# Power-Supply.net
KiCad netlist of a schematic drawn in Altium Designer
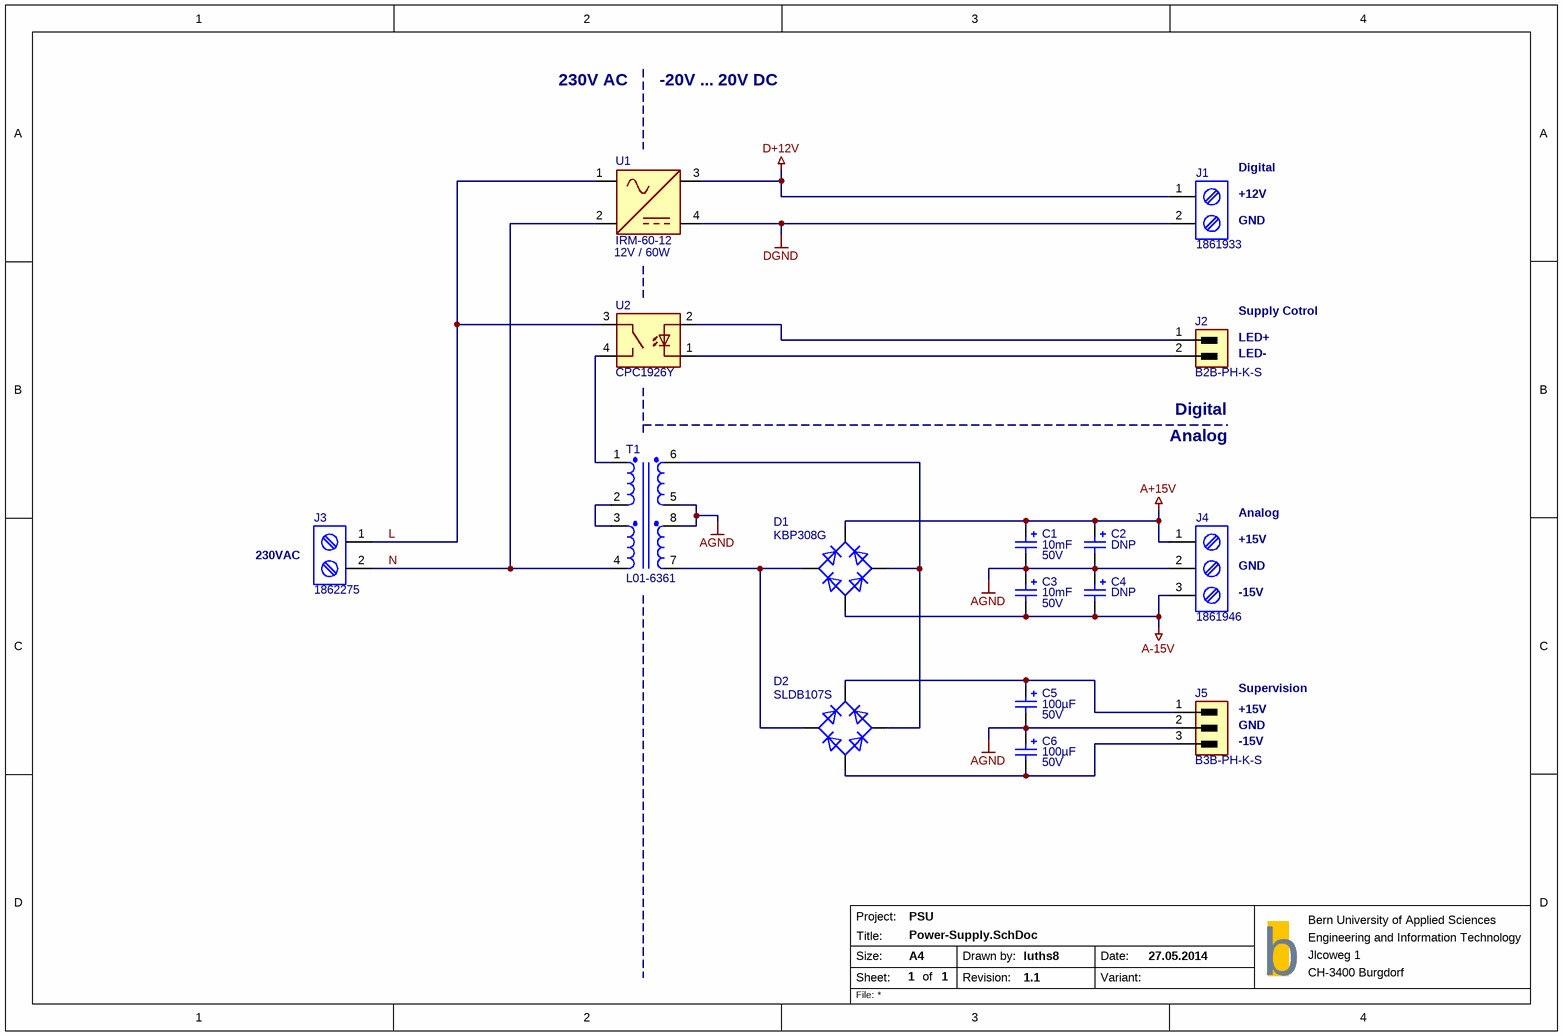
[diagram p0: Power-Supply.SchDoc]

(export (version "E")
  (design (tool "Eeschema 10.0.6"))
  (components
    (comp (ref "C1")
      (value "10mF")
      (footprint "CAP-25-50-12.5 - duplicate")
      (description "Elektrolytic Capacitor")
      (fields (field (name "VOLTAGE") "50V") (field (name "MANUFACTURER PART NO.") "UKW1H103MRD"))
      (libsource (lib "Audio-Streamer") (part "Capacitor Electrolytic"))
    )
    (comp (ref "C2")
      (value "DNP")
      (footprint "CAP-25-50-12.5 - duplicate")
      (description "Elektrolytic Capacitor")
      (fields (field (name "VOLTAGE") "50V") (field (name "MANUFACTURER PART NO.") "UKW1H103MRD"))
      (libsource (lib "Audio-Streamer") (part "Capacitor Electrolytic"))
    )
    (comp (ref "C3")
      (value "10mF")
      (footprint "CAP-25-50-12.5 - duplicate")
      (description "Elektrolytic Capacitor")
      (fields (field (name "VOLTAGE") "50V") (field (name "MANUFACTURER PART NO.") "UKW1H103MRD"))
      (libsource (lib "Audio-Streamer") (part "Capacitor Electrolytic"))
    )
    (comp (ref "C4")
      (value "DNP")
      (footprint "CAP-25-50-12.5 - duplicate")
      (description "Elektrolytic Capacitor")
      (fields (field (name "VOLTAGE") "50V") (field (name "MANUFACTURER PART NO.") "UKW1H103MRD"))
      (libsource (lib "Audio-Streamer") (part "Capacitor Electrolytic"))
    )
    (comp (ref "C5")
      (value "100µF")
      (footprint "CAP-8-11.5-3.5")
      (description "Elektrolytic Capacitor")
      (fields (field (name "VOLTAGE") "50V") (field (name "MANUFACTURER PART NO.") "EEU-FR1H101"))
      (libsource (lib "Audio-Streamer") (part "Capacitor Electrolytic"))
    )
    (comp (ref "C6")
      (value "100µF")
      (footprint "CAP-8-11.5-3.5")
      (description "Elektrolytic Capacitor")
      (fields (field (name "VOLTAGE") "50V") (field (name "MANUFACTURER PART NO.") "EEU-FR1H101"))
      (libsource (lib "Audio-Streamer") (part "Capacitor Electrolytic"))
    )
    (comp (ref "D1")
      (value "KBP308G")
      (footprint "KBP30")
      (description "Full Bridge Rectifier")
      (libsource (lib "Audio-Streamer") (part "Rectifier"))
    )
    (comp (ref "D2")
      (value "SLDB107S")
      (footprint "SLDBS-4")
      (description "Full Bridge Rectifier")
      (libsource (lib "Audio-Streamer") (part "Rectifier"))
    )
    (comp (ref "J1")
      (value "1861933")
      (footprint "1861933")
      (description "Screw Terminal, 2 Position")
      (libsource (lib "Audio-Streamer") (part "1861933"))
    )
    (comp (ref "J2")
      (value "B2B-PH-K-S")
      (footprint "B2B-PH-K-S")
      (description "Connector 2x1P")
      (libsource (lib "Audio-Streamer") (part "Connector 2x1P"))
    )
    (comp (ref "J3")
      (value "1862275")
      (footprint "1862275")
      (description "Screw Terminal, 2 Position, 5mm Spacing")
      (libsource (lib "Audio-Streamer") (part "1862275"))
    )
    (comp (ref "J4")
      (value "1861946")
      (footprint "1861946")
      (description "Screw Terminal, 3 Position")
      (libsource (lib "Audio-Streamer") (part "1861946"))
    )
    (comp (ref "J5")
      (value "B3B-PH-K-S")
      (footprint "B3B-PH-K-S")
      (description "Connector 3x1P")
      (fields (field (name "MANUFACTURER PART NO.") "B2B-PH-K-S"))
      (libsource (lib "Audio-Streamer") (part "Connector 3x1P"))
    )
    (comp (ref "T1")
      (value "L01-6361")
      (footprint "L01-6364")
      (description "Transformer")
      (libsource (lib "Audio-Streamer") (part "Transformer"))
    )
    (comp (ref "U1")
      (value "IRM-60-12")
      (footprint "IRM-606x")
      (description "AC/DC Converter (100VAC - 240VAC to 5VDC)")
      (fields (field (name "POWER") "12V / 60W"))
      (libsource (lib "Audio-Streamer") (part "ACDC Converter"))
    )
    (comp (ref "U2")
      (value "CPC1926Y")
      (footprint "CPC1926Y")
      (description "OptoMOS Solid State Relay")
      (libsource (lib "Audio-Streamer") (part "OptoMOS SSR"))
    )
  )
  (nets
    (net (code "1") (name "/L") (class "Default")
      (node (ref "J3") (pin "1") (pinfunction "1_1") (pintype "passive"))
      (node (ref "U1") (pin "1") (pinfunction "AC_1") (pintype "power_in"))
      (node (ref "U2") (pin "3") (pinfunction "3_3") (pintype "passive"))
    )
    (net (code "2") (name "/N") (class "Default")
      (node (ref "J3") (pin "2") (pinfunction "2_2") (pintype "passive"))
      (node (ref "T1") (pin "4") (pinfunction "4_4") (pintype "passive"))
      (node (ref "U1") (pin "2") (pinfunction "AC_2") (pintype "power_in"))
    )
    (net (code "3") (name "A+15V") (class "Default")
      (node (ref "C1") (pin "P") (pinfunction "P_P") (pintype "passive"))
      (node (ref "C2") (pin "P") (pinfunction "P_P") (pintype "passive"))
      (node (ref "D1") (pin "1") (pinfunction "1_1") (pintype "passive"))
      (node (ref "J4") (pin "1") (pinfunction "1_1") (pintype "passive"))
    )
    (net (code "4") (name "A-15V") (class "Default")
      (node (ref "C3") (pin "M") (pinfunction "q_M") (pintype "passive"))
      (node (ref "C4") (pin "M") (pinfunction "q_M") (pintype "passive"))
      (node (ref "D1") (pin "4") (pinfunction "4_4") (pintype "passive"))
      (node (ref "J4") (pin "3") (pinfunction "3_3") (pintype "passive"))
    )
    (net (code "5") (name "AGND") (class "Default")
      (node (ref "C1") (pin "M") (pinfunction "q_M") (pintype "passive"))
      (node (ref "C2") (pin "M") (pinfunction "q_M") (pintype "passive"))
      (node (ref "C3") (pin "P") (pinfunction "P_P") (pintype "passive"))
      (node (ref "C4") (pin "P") (pinfunction "P_P") (pintype "passive"))
      (node (ref "C5") (pin "M") (pinfunction "q_M") (pintype "passive"))
      (node (ref "C6") (pin "P") (pinfunction "P_P") (pintype "passive"))
      (node (ref "J4") (pin "2") (pinfunction "2_2") (pintype "passive"))
      (node (ref "J5") (pin "2") (pinfunction "2_2") (pintype "passive"))
      (node (ref "T1") (pin "5") (pinfunction "5_5") (pintype "passive"))
      (node (ref "T1") (pin "8") (pinfunction "8_8") (pintype "passive"))
    )
    (net (code "6") (name "D+12V") (class "Default")
      (node (ref "J1") (pin "1") (pinfunction "1_1") (pintype "passive"))
      (node (ref "U1") (pin "3") (pinfunction "V+_3") (pintype "power_in"))
    )
    (net (code "7") (name "DGND") (class "Default")
      (node (ref "J1") (pin "2") (pinfunction "2_2") (pintype "passive"))
      (node (ref "U1") (pin "4") (pinfunction "GND_4") (pintype "power_in"))
    )
    (net (code "8") (name "Net-(C5-PadP)") (class "Default")
      (node (ref "C5") (pin "P") (pinfunction "P_P") (pintype "passive"))
      (node (ref "D2") (pin "1") (pinfunction "1_1") (pintype "passive"))
      (node (ref "J5") (pin "1") (pinfunction "1_1") (pintype "passive"))
    )
    (net (code "9") (name "Net-(C6-q)") (class "Default")
      (node (ref "C6") (pin "M") (pinfunction "q_M") (pintype "passive"))
      (node (ref "D2") (pin "4") (pinfunction "4_4") (pintype "passive"))
      (node (ref "J5") (pin "3") (pinfunction "3_3") (pintype "passive"))
    )
    (net (code "10") (name "Net-(D1-Pad2)") (class "Default")
      (node (ref "D1") (pin "2") (pinfunction "2_2") (pintype "passive"))
      (node (ref "D2") (pin "2") (pinfunction "2_2") (pintype "passive"))
      (node (ref "T1") (pin "7") (pinfunction "7_7") (pintype "passive"))
    )
    (net (code "11") (name "Net-(D1-Pad3)") (class "Default")
      (node (ref "D1") (pin "3") (pinfunction "3_3") (pintype "passive"))
      (node (ref "D2") (pin "3") (pinfunction "3_3") (pintype "passive"))
      (node (ref "T1") (pin "6") (pinfunction "6_6") (pintype "passive"))
    )
    (net (code "12") (name "Net-(J2-Pad1)") (class "Default")
      (node (ref "J2") (pin "1") (pinfunction "1_1") (pintype "passive"))
      (node (ref "U2") (pin "2") (pinfunction "2_2") (pintype "passive"))
    )
    (net (code "13") (name "Net-(J2-Pad2)") (class "Default")
      (node (ref "J2") (pin "2") (pinfunction "2_2") (pintype "passive"))
      (node (ref "U2") (pin "1") (pinfunction "1_1") (pintype "passive"))
    )
    (net (code "14") (name "Net-(T1-Pad1)") (class "Default")
      (node (ref "T1") (pin "1") (pinfunction "1_1") (pintype "passive"))
      (node (ref "U2") (pin "4") (pinfunction "4_4") (pintype "passive"))
    )
    (net (code "15") (name "Net-(T1-Pad2)") (class "Default")
      (node (ref "T1") (pin "2") (pinfunction "2_2") (pintype "passive"))
      (node (ref "T1") (pin "3") (pinfunction "3_3") (pintype "passive"))
    )
  )
)
